# NAND_FLASH_MT29F2G16AABWP.net
KiCad netlist of a schematic drawn in Altium Designer
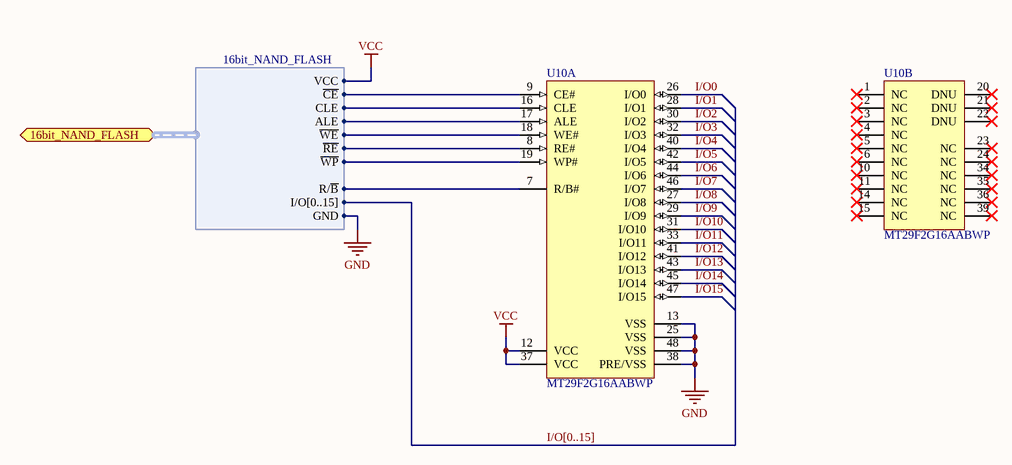
[diagram p0: NAND_FLASH_MT29F2G16AABWP.SchDoc]

(export (version "E")
  (design (tool "Eeschema 10.0.6"))
  (components
    (comp (ref "U10")
      (value "MT29F2G16AABWP")
      (footprint "MICT-WP-48_N")
      (description "2 Gb x 16 Multiplexed NAND Flash Memory, 2.7 to 3.6 V, 0 to 70 degC, 48-Pin TSOP, RoHS")
      (fields (field (name "MANUFACTURER") "Micron"))
      (libsource (lib "Altium Content Vault") (part "CMP-0760-00001-1"))
    )
  )
  (nets
    (net (code "18") (name "/ALE") (class "Default")
      (node (ref "U10") (pin "17") (pinfunction "ALE_17") (pintype "input"))
    )
    (net (code "19") (name "/CLE") (class "Default")
      (node (ref "U10") (pin "16") (pinfunction "CLE_16") (pintype "input"))
    )
    (net (code "20") (name "/I{slash}O0") (class "Default")
      (node (ref "U10") (pin "26") (pinfunction "I/O0_26") (pintype "bidirectional"))
    )
    (net (code "21") (name "/I{slash}O1") (class "Default")
      (node (ref "U10") (pin "28") (pinfunction "I/O1_28") (pintype "bidirectional"))
    )
    (net (code "22") (name "/I{slash}O2") (class "Default")
      (node (ref "U10") (pin "30") (pinfunction "I/O2_30") (pintype "bidirectional"))
    )
    (net (code "23") (name "/I{slash}O3") (class "Default")
      (node (ref "U10") (pin "32") (pinfunction "I/O3_32") (pintype "bidirectional"))
    )
    (net (code "24") (name "/I{slash}O4") (class "Default")
      (node (ref "U10") (pin "40") (pinfunction "I/O4_40") (pintype "bidirectional"))
    )
    (net (code "25") (name "/I{slash}O5") (class "Default")
      (node (ref "U10") (pin "42") (pinfunction "I/O5_42") (pintype "bidirectional"))
    )
    (net (code "26") (name "/I{slash}O6") (class "Default")
      (node (ref "U10") (pin "44") (pinfunction "I/O6_44") (pintype "bidirectional"))
    )
    (net (code "27") (name "/I{slash}O7") (class "Default")
      (node (ref "U10") (pin "46") (pinfunction "I/O7_46") (pintype "bidirectional"))
    )
    (net (code "28") (name "/I{slash}O8") (class "Default")
      (node (ref "U10") (pin "27") (pinfunction "I/O8_27") (pintype "bidirectional"))
    )
    (net (code "29") (name "/I{slash}O9") (class "Default")
      (node (ref "U10") (pin "29") (pinfunction "I/O9_29") (pintype "bidirectional"))
    )
    (net (code "30") (name "/I{slash}O10") (class "Default")
      (node (ref "U10") (pin "31") (pinfunction "I/O10_31") (pintype "bidirectional"))
    )
    (net (code "31") (name "/I{slash}O11") (class "Default")
      (node (ref "U10") (pin "33") (pinfunction "I/O11_33") (pintype "bidirectional"))
    )
    (net (code "32") (name "/I{slash}O12") (class "Default")
      (node (ref "U10") (pin "41") (pinfunction "I/O12_41") (pintype "bidirectional"))
    )
    (net (code "33") (name "/I{slash}O13") (class "Default")
      (node (ref "U10") (pin "43") (pinfunction "I/O13_43") (pintype "bidirectional"))
    )
    (net (code "34") (name "/I{slash}O14") (class "Default")
      (node (ref "U10") (pin "45") (pinfunction "I/O14_45") (pintype "bidirectional"))
    )
    (net (code "35") (name "/I{slash}O15") (class "Default")
      (node (ref "U10") (pin "47") (pinfunction "I/O15_47") (pintype "bidirectional"))
    )
    (net (code "37") (name "/R{slash}~{B}") (class "Default")
      (node (ref "U10") (pin "7") (pinfunction "R/B#_7") (pintype "tri_state"))
    )
    (net (code "39") (name "/~{CE}") (class "Default")
      (node (ref "U10") (pin "9") (pinfunction "CE#_9") (pintype "input"))
    )
    (net (code "40") (name "/~{RE}") (class "Default")
      (node (ref "U10") (pin "8") (pinfunction "RE#_8") (pintype "input"))
    )
    (net (code "41") (name "/~{WE}") (class "Default")
      (node (ref "U10") (pin "18") (pinfunction "WE#_18") (pintype "input"))
    )
    (net (code "42") (name "/~{WP}") (class "Default")
      (node (ref "U10") (pin "19") (pinfunction "WP#_19") (pintype "input"))
    )
    (net (code "43") (name "GND") (class "Default")
      (node (ref "U10") (pin "13") (pinfunction "VSS_13") (pintype "power_in"))
      (node (ref "U10") (pin "25") (pinfunction "VSS_25") (pintype "power_in"))
      (node (ref "U10") (pin "38") (pinfunction "PRE/VSS_38") (pintype "power_in"))
      (node (ref "U10") (pin "48") (pinfunction "VSS_48") (pintype "power_in"))
    )
    (net (code "44") (name "VCC") (class "Default")
      (node (ref "U10") (pin "12") (pinfunction "VCC_12") (pintype "power_in"))
      (node (ref "U10") (pin "37") (pinfunction "VCC_37") (pintype "power_in"))
    )
    (net (code "45") (name "unconnected-(U10B-DNU-Pad20)") (class "Default")
      (node (ref "U10") (pin "20") (pinfunction "DNU_20") (pintype "passive+no_connect"))
    )
    (net (code "46") (name "unconnected-(U10B-DNU-Pad21)") (class "Default")
      (node (ref "U10") (pin "21") (pinfunction "DNU_21") (pintype "passive+no_connect"))
    )
    (net (code "47") (name "unconnected-(U10B-DNU-Pad22)") (class "Default")
      (node (ref "U10") (pin "22") (pinfunction "DNU_22") (pintype "passive+no_connect"))
    )
    (net (code "48") (name "unconnected-(U10B-NC-Pad1)") (class "Default")
      (node (ref "U10") (pin "1") (pinfunction "NC_1") (pintype "passive+no_connect"))
    )
    (net (code "49") (name "unconnected-(U10B-NC-Pad2)") (class "Default")
      (node (ref "U10") (pin "2") (pinfunction "NC_2") (pintype "passive+no_connect"))
    )
    (net (code "50") (name "unconnected-(U10B-NC-Pad3)") (class "Default")
      (node (ref "U10") (pin "3") (pinfunction "NC_3") (pintype "passive+no_connect"))
    )
    (net (code "51") (name "unconnected-(U10B-NC-Pad4)") (class "Default")
      (node (ref "U10") (pin "4") (pinfunction "NC_4") (pintype "passive+no_connect"))
    )
    (net (code "52") (name "unconnected-(U10B-NC-Pad5)") (class "Default")
      (node (ref "U10") (pin "5") (pinfunction "NC_5") (pintype "passive+no_connect"))
    )
    (net (code "53") (name "unconnected-(U10B-NC-Pad6)") (class "Default")
      (node (ref "U10") (pin "6") (pinfunction "NC_6") (pintype "passive+no_connect"))
    )
    (net (code "54") (name "unconnected-(U10B-NC-Pad10)") (class "Default")
      (node (ref "U10") (pin "10") (pinfunction "NC_10") (pintype "passive+no_connect"))
    )
    (net (code "55") (name "unconnected-(U10B-NC-Pad11)") (class "Default")
      (node (ref "U10") (pin "11") (pinfunction "NC_11") (pintype "passive+no_connect"))
    )
    (net (code "56") (name "unconnected-(U10B-NC-Pad14)") (class "Default")
      (node (ref "U10") (pin "14") (pinfunction "NC_14") (pintype "passive+no_connect"))
    )
    (net (code "57") (name "unconnected-(U10B-NC-Pad15)") (class "Default")
      (node (ref "U10") (pin "15") (pinfunction "NC_15") (pintype "passive+no_connect"))
    )
    (net (code "58") (name "unconnected-(U10B-NC-Pad23)") (class "Default")
      (node (ref "U10") (pin "23") (pinfunction "NC_23") (pintype "passive+no_connect"))
    )
    (net (code "59") (name "unconnected-(U10B-NC-Pad24)") (class "Default")
      (node (ref "U10") (pin "24") (pinfunction "NC_24") (pintype "passive+no_connect"))
    )
    (net (code "60") (name "unconnected-(U10B-NC-Pad34)") (class "Default")
      (node (ref "U10") (pin "34") (pinfunction "NC_34") (pintype "passive+no_connect"))
    )
    (net (code "61") (name "unconnected-(U10B-NC-Pad35)") (class "Default")
      (node (ref "U10") (pin "35") (pinfunction "NC_35") (pintype "passive+no_connect"))
    )
    (net (code "62") (name "unconnected-(U10B-NC-Pad36)") (class "Default")
      (node (ref "U10") (pin "36") (pinfunction "NC_36") (pintype "passive+no_connect"))
    )
    (net (code "63") (name "unconnected-(U10B-NC-Pad39)") (class "Default")
      (node (ref "U10") (pin "39") (pinfunction "NC_39") (pintype "passive+no_connect"))
    )
  )
)
